# Adafruit_Prop_Maker_FeatherWing.net
KiCad netlist of a schematic drawn in EAGLE
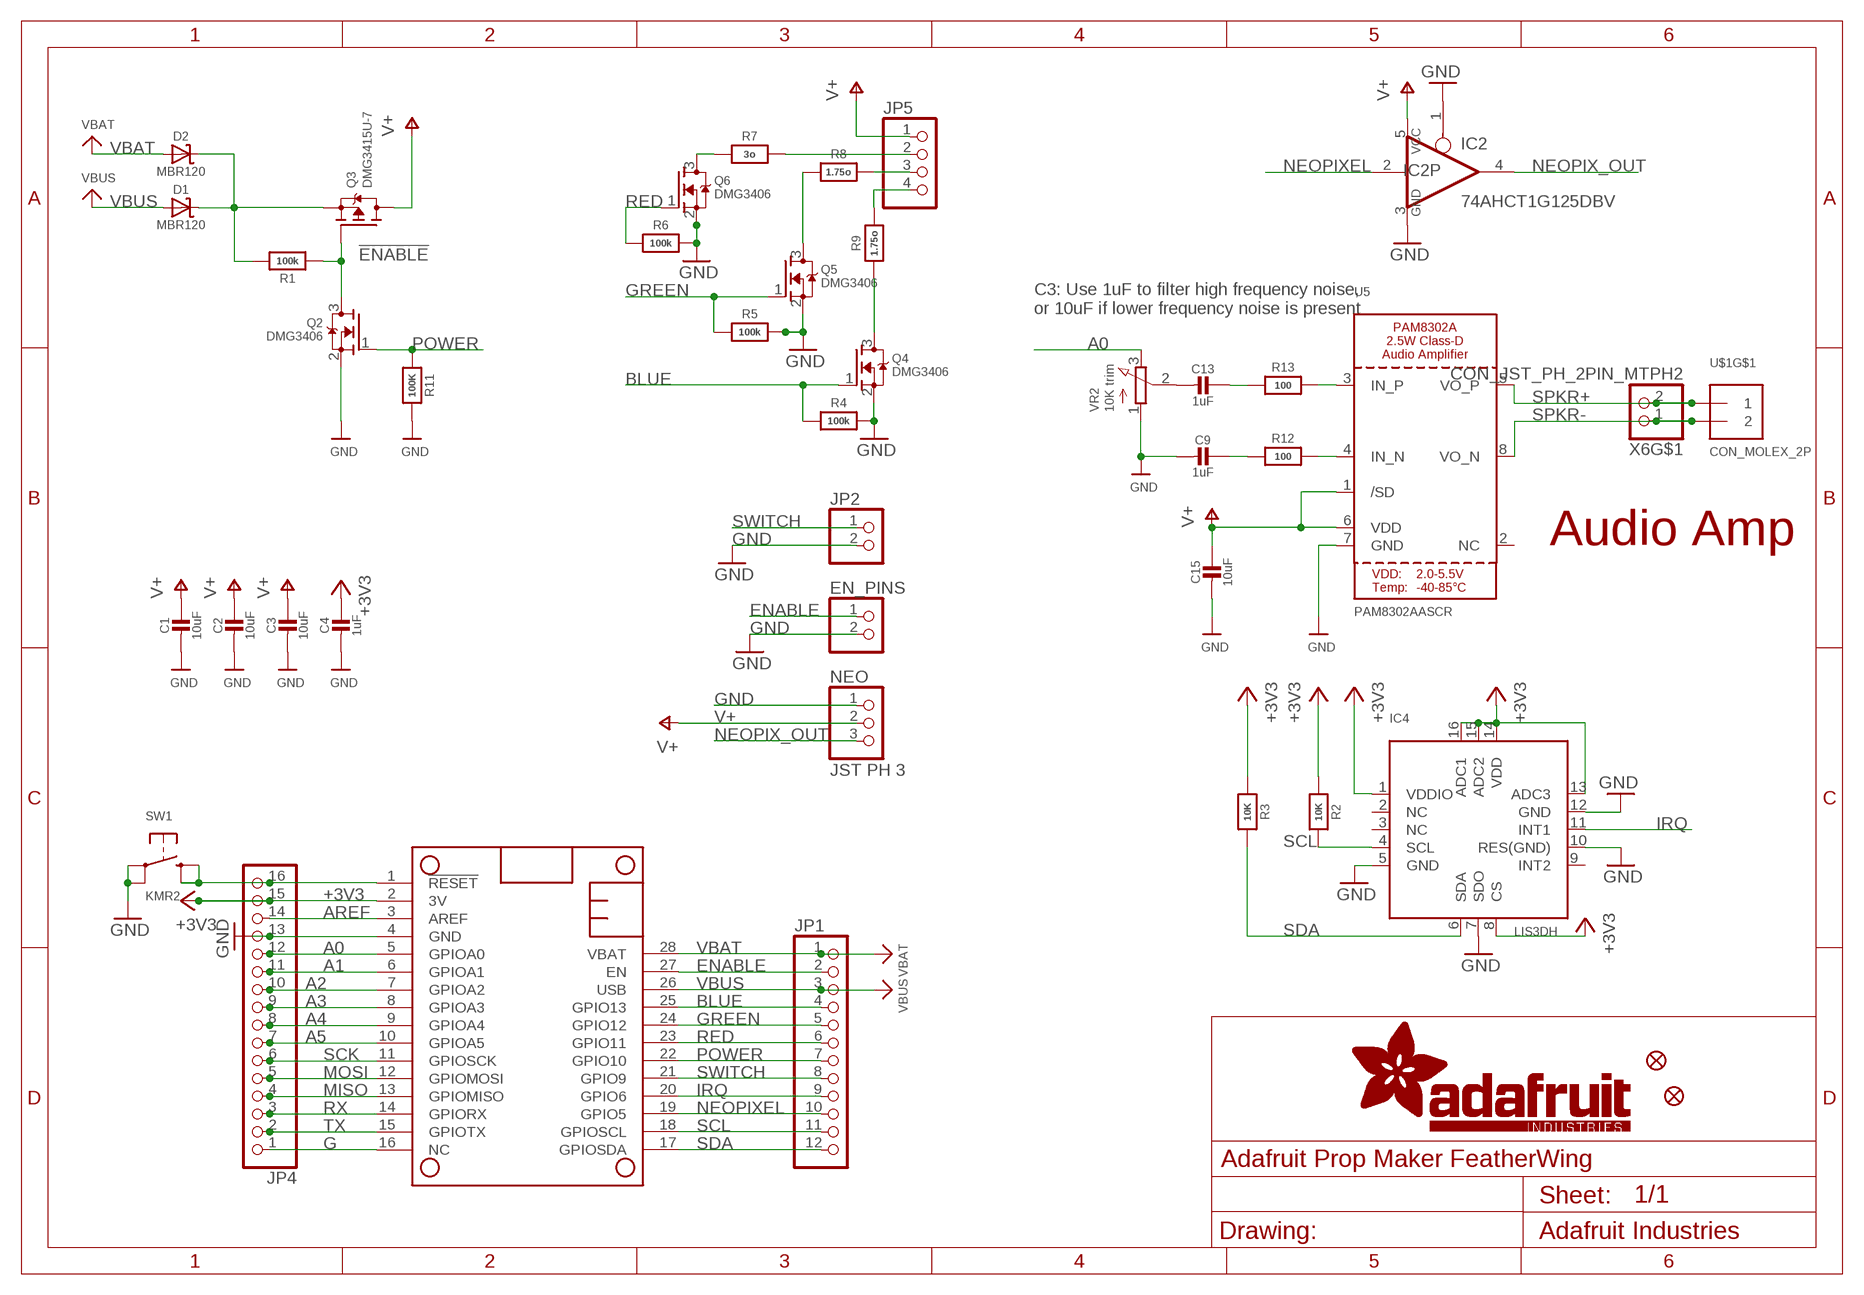
[diagram p0: schematic, sheet 1]

(export (version "E")
  (design (tool "Eeschema 10.0.6"))
  (components
    (comp (ref "C1")
      (value "10uF")
      (footprint "eagle-import:0805-NO")
      (libsource (lib "eagle-import") (part "CAP_CERAMIC0805-NOOUTLINE"))
    )
    (comp (ref "C2")
      (value "10uF")
      (footprint "eagle-import:0805-NO")
      (libsource (lib "eagle-import") (part "CAP_CERAMIC0805-NOOUTLINE"))
    )
    (comp (ref "C3")
      (value "10uF")
      (footprint "eagle-import:0805-NO")
      (libsource (lib "eagle-import") (part "CAP_CERAMIC0805-NOOUTLINE"))
    )
    (comp (ref "C4")
      (value "1uF")
      (footprint "eagle-import:0603-NO")
      (libsource (lib "eagle-import") (part "CAP_CERAMIC0603_NO"))
    )
    (comp (ref "C9")
      (value "1uF")
      (footprint "eagle-import:0603-NO")
      (libsource (lib "eagle-import") (part "CAP_CERAMIC0603_NO"))
    )
    (comp (ref "C13")
      (value "1uF")
      (footprint "eagle-import:0603-NO")
      (libsource (lib "eagle-import") (part "CAP_CERAMIC0603_NO"))
    )
    (comp (ref "C15")
      (value "10uF")
      (footprint "eagle-import:0805-NO")
      (libsource (lib "eagle-import") (part "CAP_CERAMIC0805-NOOUTLINE"))
    )
    (comp (ref "D1")
      (value "MBR120")
      (footprint "eagle-import:SOD-123")
      (libsource (lib "eagle-import") (part "DIODE-SCHOTTKYSOD-123"))
    )
    (comp (ref "D2")
      (value "MBR120")
      (footprint "eagle-import:SOD-123")
      (libsource (lib "eagle-import") (part "DIODE-SCHOTTKYSOD-123"))
    )
    (comp (ref "EN_PINS")
      (value "HEADER-1X2ROUND")
      (footprint "eagle-import:1X02_ROUND")
      (libsource (lib "eagle-import") (part "HEADER-1X2ROUND"))
    )
    (comp (ref "FID1")
      (value "FIDUCIAL_1MM")
      (footprint "eagle-import:FIDUCIAL_1MM")
      (libsource (lib "eagle-import") (part "FIDUCIAL_1MM"))
    )
    (comp (ref "FID3")
      (value "FIDUCIAL_1MM")
      (footprint "eagle-import:FIDUCIAL_1MM")
      (libsource (lib "eagle-import") (part "FIDUCIAL_1MM"))
    )
    (comp (ref "IC2")
      (value "74AHCT1G125DBV")
      (footprint "eagle-import:SOT23-5")
      (libsource (lib "eagle-import") (part "741G125DBVAHCT"))
    )
    (comp (ref "IC4")
      (value "LIS3DH")
      (footprint "eagle-import:LGA16_3X3MM")
      (libsource (lib "eagle-import") (part "ACCEL_LIS3DHTR"))
    )
    (comp (ref "JP1")
      (value "HEADER-1X12")
      (footprint "eagle-import:1X12_ROUND")
      (libsource (lib "eagle-import") (part "HEADER-1X12"))
    )
    (comp (ref "JP2")
      (value "HEADER-1X2ROUND")
      (footprint "eagle-import:1X02_ROUND")
      (libsource (lib "eagle-import") (part "HEADER-1X2ROUND"))
    )
    (comp (ref "JP4")
      (value "HEADER-1X16ROUND")
      (footprint "eagle-import:1X16_ROUND")
      (libsource (lib "eagle-import") (part "HEADER-1X16ROUND"))
    )
    (comp (ref "JP5")
      (value "HEADER-1X4ROUND")
      (footprint "eagle-import:1X04_ROUND")
      (libsource (lib "eagle-import") (part "HEADER-1X4ROUND"))
    )
    (comp (ref "MS1")
      (value "FEATHERWING")
      (footprint "eagle-import:FEATHERWING")
      (libsource (lib "eagle-import") (part "FEATHERWING"))
    )
    (comp (ref "NEO")
      (value "JST PH 3")
      (footprint "eagle-import:JSTPH3")
      (libsource (lib "eagle-import") (part "CON_JST_PH_3PIN"))
    )
    (comp (ref "Q2")
      (value "DMG3406")
      (footprint "eagle-import:SOT23-WIDE")
      (libsource (lib "eagle-import") (part "MOSFET-NWIDE"))
    )
    (comp (ref "Q3")
      (value "DMG3415U-7")
      (footprint "eagle-import:SOT23-WIDE")
      (libsource (lib "eagle-import") (part "MOSFET-PWIDE"))
    )
    (comp (ref "Q4")
      (value "DMG3406")
      (footprint "eagle-import:SOT23-WIDE")
      (libsource (lib "eagle-import") (part "MOSFET-NWIDE"))
    )
    (comp (ref "Q5")
      (value "DMG3406")
      (footprint "eagle-import:SOT23-WIDE")
      (libsource (lib "eagle-import") (part "MOSFET-NWIDE"))
    )
    (comp (ref "Q6")
      (value "DMG3406")
      (footprint "eagle-import:SOT23-WIDE")
      (libsource (lib "eagle-import") (part "MOSFET-NWIDE"))
    )
    (comp (ref "R1")
      (value "100k")
      (footprint "eagle-import:0603-NO")
      (libsource (lib "eagle-import") (part "RESISTOR_0603_NOOUT"))
    )
    (comp (ref "R2")
      (value "10K")
      (footprint "eagle-import:0603-NO")
      (libsource (lib "eagle-import") (part "RESISTOR_0603_NOOUT"))
    )
    (comp (ref "R3")
      (value "10K")
      (footprint "eagle-import:0603-NO")
      (libsource (lib "eagle-import") (part "RESISTOR_0603_NOOUT"))
    )
    (comp (ref "R4")
      (value "100k")
      (footprint "eagle-import:0603-NO")
      (libsource (lib "eagle-import") (part "RESISTOR_0603_NOOUT"))
    )
    (comp (ref "R5")
      (value "100k")
      (footprint "eagle-import:0603-NO")
      (libsource (lib "eagle-import") (part "RESISTOR_0603_NOOUT"))
    )
    (comp (ref "R6")
      (value "100k")
      (footprint "eagle-import:0603-NO")
      (libsource (lib "eagle-import") (part "RESISTOR_0603_NOOUT"))
    )
    (comp (ref "R7")
      (value "3o")
      (footprint "eagle-import:_1206")
      (libsource (lib "eagle-import") (part "RESISTOR_1206"))
    )
    (comp (ref "R8")
      (value "1.75o")
      (footprint "eagle-import:_1206")
      (libsource (lib "eagle-import") (part "RESISTOR_1206"))
    )
    (comp (ref "R9")
      (value "1.75o")
      (footprint "eagle-import:_1206")
      (libsource (lib "eagle-import") (part "RESISTOR_1206"))
    )
    (comp (ref "R11")
      (value "100K")
      (footprint "eagle-import:0603-NO")
      (libsource (lib "eagle-import") (part "RESISTOR_0603_NOOUT"))
    )
    (comp (ref "R12")
      (value "100")
      (footprint "eagle-import:0603-NO")
      (libsource (lib "eagle-import") (part "RESISTOR_0603_NOOUT"))
    )
    (comp (ref "R13")
      (value "100")
      (footprint "eagle-import:0603-NO")
      (libsource (lib "eagle-import") (part "RESISTOR_0603_NOOUT"))
    )
    (comp (ref "SW1")
      (value "KMR2")
      (footprint "eagle-import:BTN_KMR2_4.6X2.8")
      (libsource (lib "eagle-import") (part "SWITCH_TACT_SMT4.6X2.8"))
    )
    (comp (ref "U$1")
      (value "CON_MOLEX_2P")
      (footprint "eagle-import:53398-0271")
      (libsource (lib "eagle-import") (part "CON_MOLEX_2P"))
    )
    (comp (ref "U5")
      (value "PAM8302AASCR")
      (footprint "eagle-import:MSOP8_0.65MM")
      (libsource (lib "eagle-import") (part "AUDIOAMP_PAM8302A"))
    )
    (comp (ref "VR2")
      (value "10K trim")
      (footprint "eagle-import:TRIMPOT_BOURNS_3303W")
      (libsource (lib "eagle-import") (part "TRIMPOT3303W/X"))
    )
    (comp (ref "X6")
      (value "CON_JST_PH_2PIN_MTPH2")
      (footprint "eagle-import:JSTPH2")
      (libsource (lib "eagle-import") (part "CON_JST_PH_2PIN_MTPH2"))
    )
  )
  (nets
    (net (code "1") (name "+3V3") (class "Default")
      (node (ref "C4") (pin "1") (pinfunction "1_1") (pintype "passive"))
      (node (ref "IC4") (pin "1") (pinfunction "VDDIO_1") (pintype "power_in"))
      (node (ref "IC4") (pin "13") (pinfunction "ADC3_13") (pintype "input"))
      (node (ref "IC4") (pin "14") (pinfunction "VDD_14") (pintype "power_in"))
      (node (ref "IC4") (pin "15") (pinfunction "ADC2_15") (pintype "input"))
      (node (ref "IC4") (pin "16") (pinfunction "ADC1_16") (pintype "input"))
      (node (ref "IC4") (pin "8") (pinfunction "CS_8") (pintype "input"))
      (node (ref "JP4") (pin "15") (pinfunction "15_15") (pintype "passive"))
      (node (ref "MS1") (pin "2") (pinfunction "3V_2") (pintype "power_in"))
      (node (ref "R2") (pin "1") (pinfunction "1_1") (pintype "passive"))
      (node (ref "R3") (pin "1") (pinfunction "1_1") (pintype "passive"))
    )
    (net (code "2") (name "/A0") (class "Default")
      (node (ref "JP4") (pin "12") (pinfunction "12_12") (pintype "passive"))
      (node (ref "MS1") (pin "5") (pinfunction "GPIOA0_5") (pintype "bidirectional"))
      (node (ref "VR2") (pin "3") (pinfunction "E_3") (pintype "passive"))
    )
    (net (code "3") (name "/A1") (class "Default")
      (node (ref "JP4") (pin "11") (pinfunction "11_11") (pintype "passive"))
      (node (ref "MS1") (pin "6") (pinfunction "GPIOA1_6") (pintype "bidirectional"))
    )
    (net (code "4") (name "/A2") (class "Default")
      (node (ref "JP4") (pin "10") (pinfunction "10_10") (pintype "passive"))
      (node (ref "MS1") (pin "7") (pinfunction "GPIOA2_7") (pintype "bidirectional"))
    )
    (net (code "5") (name "/A3") (class "Default")
      (node (ref "JP4") (pin "9") (pinfunction "9_9") (pintype "passive"))
      (node (ref "MS1") (pin "8") (pinfunction "GPIOA3_8") (pintype "bidirectional"))
    )
    (net (code "6") (name "/A4") (class "Default")
      (node (ref "JP4") (pin "8") (pinfunction "8_8") (pintype "passive"))
      (node (ref "MS1") (pin "9") (pinfunction "GPIOA4_9") (pintype "bidirectional"))
    )
    (net (code "7") (name "/A5") (class "Default")
      (node (ref "JP4") (pin "7") (pinfunction "7_7") (pintype "passive"))
      (node (ref "MS1") (pin "10") (pinfunction "GPIOA5_10") (pintype "bidirectional"))
    )
    (net (code "8") (name "/AREF") (class "Default")
      (node (ref "JP4") (pin "14") (pinfunction "14_14") (pintype "passive"))
      (node (ref "MS1") (pin "3") (pinfunction "AREF_3") (pintype "passive"))
    )
    (net (code "9") (name "/BLUE") (class "Default")
      (node (ref "JP1") (pin "4") (pinfunction "4_4") (pintype "passive"))
      (node (ref "MS1") (pin "25") (pinfunction "GPIO13_25") (pintype "bidirectional"))
      (node (ref "Q4") (pin "1") (pinfunction "G_1") (pintype "bidirectional"))
      (node (ref "R4") (pin "1") (pinfunction "1_1") (pintype "passive"))
    )
    (net (code "10") (name "/ENABLE") (class "Default")
      (node (ref "EN_PINS") (pin "1") (pinfunction "1_1") (pintype "passive"))
      (node (ref "JP1") (pin "2") (pinfunction "2_2") (pintype "passive"))
      (node (ref "MS1") (pin "27") (pinfunction "EN_27") (pintype "passive"))
    )
    (net (code "11") (name "/G") (class "Default")
      (node (ref "JP4") (pin "1") (pinfunction "1_1") (pintype "passive"))
      (node (ref "MS1") (pin "16") (pinfunction "NC_16") (pintype "passive"))
    )
    (net (code "12") (name "/GREEN") (class "Default")
      (node (ref "JP1") (pin "5") (pinfunction "5_5") (pintype "passive"))
      (node (ref "MS1") (pin "24") (pinfunction "GPIO12_24") (pintype "bidirectional"))
      (node (ref "Q5") (pin "1") (pinfunction "G_1") (pintype "bidirectional"))
      (node (ref "R5") (pin "1") (pinfunction "1_1") (pintype "passive"))
    )
    (net (code "13") (name "/IRQ") (class "Default")
      (node (ref "IC4") (pin "11") (pinfunction "INT1_11") (pintype "output"))
      (node (ref "JP1") (pin "9") (pinfunction "9_9") (pintype "passive"))
      (node (ref "MS1") (pin "20") (pinfunction "GPIO6_20") (pintype "bidirectional"))
    )
    (net (code "14") (name "/MISO") (class "Default")
      (node (ref "JP4") (pin "4") (pinfunction "4_4") (pintype "passive"))
      (node (ref "MS1") (pin "13") (pinfunction "GPIOMISO_13") (pintype "bidirectional"))
    )
    (net (code "15") (name "/MOSI") (class "Default")
      (node (ref "JP4") (pin "5") (pinfunction "5_5") (pintype "passive"))
      (node (ref "MS1") (pin "12") (pinfunction "GPIOMOSI_12") (pintype "bidirectional"))
    )
    (net (code "16") (name "/NEOPIXEL") (class "Default")
      (node (ref "IC2") (pin "2") (pinfunction "I_2") (pintype "input"))
      (node (ref "JP1") (pin "10") (pinfunction "10_10") (pintype "passive"))
      (node (ref "MS1") (pin "19") (pinfunction "GPIO5_19") (pintype "bidirectional"))
    )
    (net (code "17") (name "/NEOPIX_OUT") (class "Default")
      (node (ref "IC2") (pin "4") (pinfunction "O_4") (pintype "tri_state"))
      (node (ref "NEO") (pin "3") (pinfunction "3_3") (pintype "passive"))
    )
    (net (code "18") (name "/POWER") (class "Default")
      (node (ref "JP1") (pin "7") (pinfunction "7_7") (pintype "passive"))
      (node (ref "MS1") (pin "22") (pinfunction "GPIO10_22") (pintype "bidirectional"))
      (node (ref "Q2") (pin "1") (pinfunction "G_1") (pintype "bidirectional"))
      (node (ref "R11") (pin "1") (pinfunction "1_1") (pintype "passive"))
    )
    (net (code "19") (name "/RED") (class "Default")
      (node (ref "JP1") (pin "6") (pinfunction "6_6") (pintype "passive"))
      (node (ref "MS1") (pin "23") (pinfunction "GPIO11_23") (pintype "bidirectional"))
      (node (ref "Q6") (pin "1") (pinfunction "G_1") (pintype "bidirectional"))
      (node (ref "R6") (pin "1") (pinfunction "1_1") (pintype "passive"))
    )
    (net (code "20") (name "/RX") (class "Default")
      (node (ref "JP4") (pin "3") (pinfunction "3_3") (pintype "passive"))
      (node (ref "MS1") (pin "14") (pinfunction "GPIORX_14") (pintype "bidirectional"))
    )
    (net (code "21") (name "/SCK") (class "Default")
      (node (ref "JP4") (pin "6") (pinfunction "6_6") (pintype "passive"))
      (node (ref "MS1") (pin "11") (pinfunction "GPIOSCK_11") (pintype "bidirectional"))
    )
    (net (code "22") (name "/SCL") (class "Default")
      (node (ref "IC4") (pin "4") (pinfunction "SCL_4") (pintype "bidirectional"))
      (node (ref "JP1") (pin "11") (pinfunction "11_11") (pintype "passive"))
      (node (ref "MS1") (pin "18") (pinfunction "GPIOSCL_18") (pintype "bidirectional"))
      (node (ref "R2") (pin "2") (pinfunction "2_2") (pintype "passive"))
    )
    (net (code "23") (name "/SDA") (class "Default")
      (node (ref "IC4") (pin "6") (pinfunction "SDA_6") (pintype "bidirectional"))
      (node (ref "JP1") (pin "12") (pinfunction "12_12") (pintype "passive"))
      (node (ref "MS1") (pin "17") (pinfunction "GPIOSDA_17") (pintype "bidirectional"))
      (node (ref "R3") (pin "2") (pinfunction "2_2") (pintype "passive"))
    )
    (net (code "24") (name "/SPKR+") (class "Default")
      (node (ref "U$1") (pin "1") (pinfunction "1_1") (pintype "passive"))
      (node (ref "U5") (pin "5") (pinfunction "VO_P_5") (pintype "output"))
      (node (ref "X6") (pin "2") (pinfunction "2_2") (pintype "passive"))
    )
    (net (code "25") (name "/SPKR-") (class "Default")
      (node (ref "U$1") (pin "2") (pinfunction "2_2") (pintype "passive"))
      (node (ref "U5") (pin "8") (pinfunction "VO_N_8") (pintype "output"))
      (node (ref "X6") (pin "1") (pinfunction "1_1") (pintype "passive"))
    )
    (net (code "26") (name "/SWITCH") (class "Default")
      (node (ref "JP1") (pin "8") (pinfunction "8_8") (pintype "passive"))
      (node (ref "JP2") (pin "1") (pinfunction "1_1") (pintype "passive"))
      (node (ref "MS1") (pin "21") (pinfunction "GPIO9_21") (pintype "bidirectional"))
    )
    (net (code "27") (name "/TX") (class "Default")
      (node (ref "JP4") (pin "2") (pinfunction "2_2") (pintype "passive"))
      (node (ref "MS1") (pin "15") (pinfunction "GPIOTX_15") (pintype "bidirectional"))
    )
    (net (code "28") (name "/~{ENABLE}") (class "Default")
      (node (ref "Q2") (pin "3") (pinfunction "D_3") (pintype "bidirectional"))
      (node (ref "Q3") (pin "1") (pinfunction "G_1") (pintype "passive"))
      (node (ref "R1") (pin "1") (pinfunction "1_1") (pintype "passive"))
    )
    (net (code "29") (name "GND") (class "Default")
      (node (ref "C1") (pin "2") (pinfunction "2_2") (pintype "passive"))
      (node (ref "C15") (pin "2") (pinfunction "2_2") (pintype "passive"))
      (node (ref "C2") (pin "2") (pinfunction "2_2") (pintype "passive"))
      (node (ref "C3") (pin "2") (pinfunction "2_2") (pintype "passive"))
      (node (ref "C4") (pin "2") (pinfunction "2_2") (pintype "passive"))
      (node (ref "C9") (pin "2") (pinfunction "2_2") (pintype "passive"))
      (node (ref "EN_PINS") (pin "2") (pinfunction "2_2") (pintype "passive"))
      (node (ref "IC2") (pin "1") (pinfunction "OE_1") (pintype "input"))
      (node (ref "IC2") (pin "3") (pinfunction "GND_3") (pintype "power_in"))
      (node (ref "IC4") (pin "10") (pinfunction "RES(GND)_10") (pintype "bidirectional"))
      (node (ref "IC4") (pin "12") (pinfunction "GND_12") (pintype "power_in"))
      (node (ref "IC4") (pin "5") (pinfunction "GND_5") (pintype "power_in"))
      (node (ref "IC4") (pin "7") (pinfunction "SDO_7") (pintype "bidirectional"))
      (node (ref "JP2") (pin "2") (pinfunction "2_2") (pintype "passive"))
      (node (ref "JP4") (pin "13") (pinfunction "13_13") (pintype "passive"))
      (node (ref "MS1") (pin "4") (pinfunction "GND_4") (pintype "power_in"))
      (node (ref "NEO") (pin "1") (pinfunction "1_1") (pintype "passive"))
      (node (ref "Q2") (pin "2") (pinfunction "S_2") (pintype "bidirectional"))
      (node (ref "Q4") (pin "2") (pinfunction "S_2") (pintype "bidirectional"))
      (node (ref "Q5") (pin "2") (pinfunction "S_2") (pintype "bidirectional"))
      (node (ref "Q6") (pin "2") (pinfunction "S_2") (pintype "bidirectional"))
      (node (ref "R11") (pin "2") (pinfunction "2_2") (pintype "passive"))
      (node (ref "R4") (pin "2") (pinfunction "2_2") (pintype "passive"))
      (node (ref "R5") (pin "2") (pinfunction "2_2") (pintype "passive"))
      (node (ref "R6") (pin "2") (pinfunction "2_2") (pintype "passive"))
      (node (ref "SW1") (pin "A") (pinfunction "P_A") (pintype "passive"))
      (node (ref "SW1") (pin "A'") (pinfunction "P1_A'") (pintype "passive"))
      (node (ref "U5") (pin "7") (pinfunction "GND_7") (pintype "power_in"))
      (node (ref "VR2") (pin "1") (pinfunction "A_1") (pintype "passive"))
    )
    (net (code "30") (name "Net-(C9-Pad1)") (class "Default")
      (node (ref "C9") (pin "1") (pinfunction "1_1") (pintype "passive"))
      (node (ref "R12") (pin "1") (pinfunction "1_1") (pintype "passive"))
    )
    (net (code "31") (name "Net-(C13-Pad1)") (class "Default")
      (node (ref "C13") (pin "1") (pinfunction "1_1") (pintype "passive"))
      (node (ref "R13") (pin "1") (pinfunction "1_1") (pintype "passive"))
    )
    (net (code "32") (name "Net-(JP5-Pad2)") (class "Default")
      (node (ref "JP5") (pin "2") (pinfunction "2_2") (pintype "passive"))
      (node (ref "R7") (pin "2") (pinfunction "2_2") (pintype "passive"))
    )
    (net (code "33") (name "Net-(JP5-Pad3)") (class "Default")
      (node (ref "JP5") (pin "3") (pinfunction "3_3") (pintype "passive"))
      (node (ref "R8") (pin "2") (pinfunction "2_2") (pintype "passive"))
    )
    (net (code "34") (name "Net-(JP5-Pad4)") (class "Default")
      (node (ref "JP5") (pin "4") (pinfunction "4_4") (pintype "passive"))
      (node (ref "R9") (pin "2") (pinfunction "2_2") (pintype "passive"))
    )
    (net (code "35") (name "Net-(MS1-~{RESET})") (class "Default")
      (node (ref "JP4") (pin "16") (pinfunction "16_16") (pintype "passive"))
      (node (ref "MS1") (pin "1") (pinfunction "~{RESET}_1") (pintype "input"))
      (node (ref "SW1") (pin "B") (pinfunction "S_B") (pintype "passive"))
      (node (ref "SW1") (pin "B'") (pinfunction "S1_B'") (pintype "passive"))
    )
    (net (code "36") (name "Net-(Q3-S)") (class "Default")
      (node (ref "D1") (pin "C") (pinfunction "C_C") (pintype "passive"))
      (node (ref "D2") (pin "C") (pinfunction "C_C") (pintype "passive"))
      (node (ref "Q3") (pin "2") (pinfunction "S_2") (pintype "passive"))
      (node (ref "R1") (pin "2") (pinfunction "2_2") (pintype "passive"))
    )
    (net (code "37") (name "Net-(Q4-D)") (class "Default")
      (node (ref "Q4") (pin "3") (pinfunction "D_3") (pintype "bidirectional"))
      (node (ref "R9") (pin "1") (pinfunction "1_1") (pintype "passive"))
    )
    (net (code "38") (name "Net-(Q5-D)") (class "Default")
      (node (ref "Q5") (pin "3") (pinfunction "D_3") (pintype "bidirectional"))
      (node (ref "R8") (pin "1") (pinfunction "1_1") (pintype "passive"))
    )
    (net (code "39") (name "Net-(Q6-D)") (class "Default")
      (node (ref "Q6") (pin "3") (pinfunction "D_3") (pintype "bidirectional"))
      (node (ref "R7") (pin "1") (pinfunction "1_1") (pintype "passive"))
    )
    (net (code "40") (name "Net-(U5-IN_N)") (class "Default")
      (node (ref "R12") (pin "2") (pinfunction "2_2") (pintype "passive"))
      (node (ref "U5") (pin "4") (pinfunction "IN_N_4") (pintype "input"))
    )
    (net (code "41") (name "Net-(U5-IN_P)") (class "Default")
      (node (ref "R13") (pin "2") (pinfunction "2_2") (pintype "passive"))
      (node (ref "U5") (pin "3") (pinfunction "IN_P_3") (pintype "input"))
    )
    (net (code "42") (name "Net-(VR2-S)") (class "Default")
      (node (ref "C13") (pin "2") (pinfunction "2_2") (pintype "passive"))
      (node (ref "VR2") (pin "2") (pinfunction "S_2") (pintype "passive"))
    )
    (net (code "43") (name "V+") (class "Default")
      (node (ref "C1") (pin "1") (pinfunction "1_1") (pintype "passive"))
      (node (ref "C15") (pin "1") (pinfunction "1_1") (pintype "passive"))
      (node (ref "C2") (pin "1") (pinfunction "1_1") (pintype "passive"))
      (node (ref "C3") (pin "1") (pinfunction "1_1") (pintype "passive"))
      (node (ref "IC2") (pin "5") (pinfunction "VCC_5") (pintype "power_in"))
      (node (ref "JP5") (pin "1") (pinfunction "1_1") (pintype "passive"))
      (node (ref "NEO") (pin "2") (pinfunction "2_2") (pintype "passive"))
      (node (ref "Q3") (pin "3") (pinfunction "D_3") (pintype "passive"))
      (node (ref "U5") (pin "1") (pinfunction "/SD_1") (pintype "input"))
      (node (ref "U5") (pin "6") (pinfunction "VDD_6") (pintype "power_in"))
    )
    (net (code "44") (name "VBAT") (class "Default")
      (node (ref "D2") (pin "A") (pinfunction "A_A") (pintype "passive"))
      (node (ref "JP1") (pin "1") (pinfunction "1_1") (pintype "passive"))
      (node (ref "MS1") (pin "28") (pinfunction "VBAT_28") (pintype "power_in"))
    )
    (net (code "45") (name "VBUS") (class "Default")
      (node (ref "D1") (pin "A") (pinfunction "A_A") (pintype "passive"))
      (node (ref "JP1") (pin "3") (pinfunction "3_3") (pintype "passive"))
      (node (ref "MS1") (pin "26") (pinfunction "USB_26") (pintype "power_in"))
    )
    (net (code "46") (name "unconnected-(IC4-INT2-Pad9)") (class "Default")
      (node (ref "IC4") (pin "9") (pinfunction "INT2_9") (pintype "output"))
    )
    (net (code "47") (name "unconnected-(IC4-NC-Pad2)") (class "Default")
      (node (ref "IC4") (pin "2") (pinfunction "NC_2") (pintype "no_connect"))
    )
    (net (code "48") (name "unconnected-(IC4-NC-Pad3)") (class "Default")
      (node (ref "IC4") (pin "3") (pinfunction "NC_3") (pintype "no_connect"))
    )
    (net (code "49") (name "unconnected-(U5-NC-Pad2)") (class "Default")
      (node (ref "U5") (pin "2") (pinfunction "NC_2") (pintype "no_connect"))
    )
  )
)
